# switcher.net
KiCad netlist of a schematic drawn in EAGLE
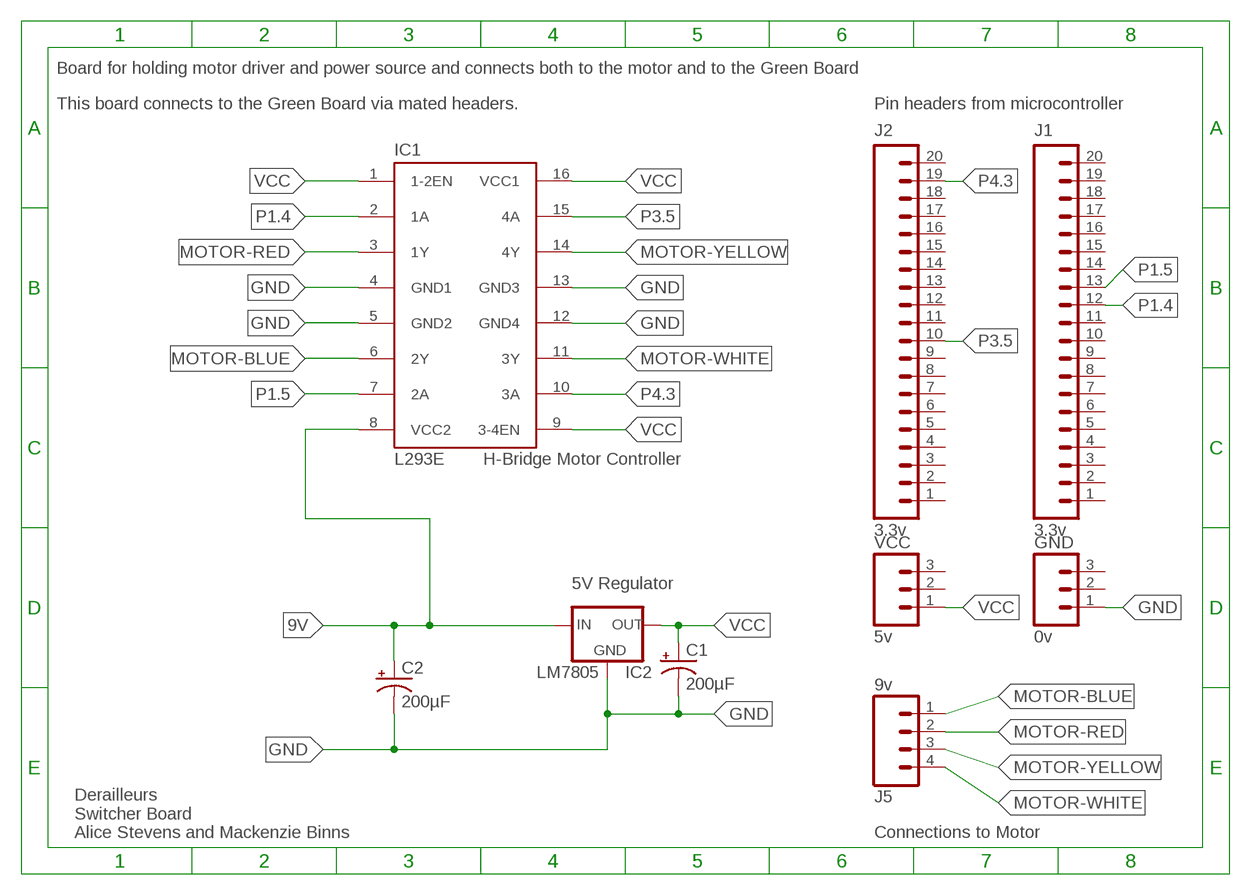
[diagram p0: schematic, sheet 1]

(export (version "E")
  (design (tool "Eeschema 10.0.6"))
  (components
    (comp (ref "C1")
      (value "200µF")
      (footprint "eagle-import:CPOL-RADIAL-100UF-25V")
      (libsource (lib "eagle-import") (part "CAP_POLPTH1"))
    )
    (comp (ref "C2")
      (value "200µF")
      (footprint "eagle-import:CPOL-RADIAL-100UF-25V")
      (libsource (lib "eagle-import") (part "CAP_POLPTH1"))
    )
    (comp (ref "GND")
      (value "0v")
      (footprint "eagle-import:1X03")
      (libsource (lib "eagle-import") (part "M03PTH"))
    )
    (comp (ref "IC1")
      (value "L293E")
      (footprint "eagle-import:DIL16")
      (fields (field (name "MF") "Arrow Electronics"))
      (libsource (lib "eagle-import") (part "L293E"))
    )
    (comp (ref "IC2")
      (value "78XXL")
      (footprint "eagle-import:78XXL")
      (libsource (lib "eagle-import") (part "78XXL"))
    )
    (comp (ref "J1")
      (value "3.3v")
      (footprint "eagle-import:1X20")
      (libsource (lib "eagle-import") (part "M20"))
    )
    (comp (ref "J2")
      (value "3.3v")
      (footprint "eagle-import:1X20")
      (libsource (lib "eagle-import") (part "M20"))
    )
    (comp (ref "J5")
      (value "9v")
      (footprint "eagle-import:1X04")
      (libsource (lib "eagle-import") (part "M04PTH"))
    )
    (comp (ref "VCC")
      (value "5v")
      (footprint "eagle-import:1X03")
      (libsource (lib "eagle-import") (part "M03PTH"))
    )
  )
  (nets
    (net (code "1") (name "9V") (class "Default")
      (node (ref "C2") (pin "1") (pinfunction "+_1") (pintype "passive"))
      (node (ref "IC1") (pin "8") (pinfunction "VCC2_8") (pintype "power_in"))
      (node (ref "IC2") (pin "IN") (pinfunction "IN_IN") (pintype "input"))
    )
    (net (code "2") (name "GND") (class "Default")
      (node (ref "C1") (pin "2") (pinfunction "-_2") (pintype "passive"))
      (node (ref "C2") (pin "2") (pinfunction "-_2") (pintype "passive"))
      (node (ref "GND") (pin "1") (pinfunction "1_1") (pintype "passive"))
      (node (ref "IC1") (pin "12") (pinfunction "GND4_12") (pintype "power_in"))
      (node (ref "IC1") (pin "13") (pinfunction "GND3_13") (pintype "power_in"))
      (node (ref "IC1") (pin "4") (pinfunction "GND1_4") (pintype "power_in"))
      (node (ref "IC1") (pin "5") (pinfunction "GND2_5") (pintype "power_in"))
      (node (ref "IC2") (pin "GND") (pinfunction "GND_GND") (pintype "input"))
    )
    (net (code "3") (name "MOTOR-BLUE") (class "Default")
      (node (ref "IC1") (pin "6") (pinfunction "2Y_6") (pintype "output"))
      (node (ref "J5") (pin "1") (pinfunction "1_1") (pintype "passive"))
    )
    (net (code "4") (name "MOTOR-RED") (class "Default")
      (node (ref "IC1") (pin "3") (pinfunction "1Y_3") (pintype "output"))
      (node (ref "J5") (pin "2") (pinfunction "2_2") (pintype "passive"))
    )
    (net (code "5") (name "MOTOR-WHITE") (class "Default")
      (node (ref "IC1") (pin "11") (pinfunction "3Y_11") (pintype "output"))
      (node (ref "J5") (pin "4") (pinfunction "4_4") (pintype "passive"))
    )
    (net (code "6") (name "MOTOR-YELLOW") (class "Default")
      (node (ref "IC1") (pin "14") (pinfunction "4Y_14") (pintype "output"))
      (node (ref "J5") (pin "3") (pinfunction "3_3") (pintype "passive"))
    )
    (net (code "7") (name "P1.4") (class "Default")
      (node (ref "IC1") (pin "2") (pinfunction "1A_2") (pintype "input"))
      (node (ref "J1") (pin "12") (pinfunction "12_12") (pintype "passive"))
    )
    (net (code "8") (name "P1.5") (class "Default")
      (node (ref "IC1") (pin "7") (pinfunction "2A_7") (pintype "input"))
      (node (ref "J1") (pin "13") (pinfunction "13_13") (pintype "passive"))
    )
    (net (code "9") (name "P3.5") (class "Default")
      (node (ref "IC1") (pin "15") (pinfunction "4A_15") (pintype "input"))
      (node (ref "J2") (pin "10") (pinfunction "10_10") (pintype "passive"))
    )
    (net (code "10") (name "P4.3") (class "Default")
      (node (ref "IC1") (pin "10") (pinfunction "3A_10") (pintype "input"))
      (node (ref "J2") (pin "19") (pinfunction "19_19") (pintype "passive"))
    )
    (net (code "11") (name "VCC") (class "Default")
      (node (ref "C1") (pin "1") (pinfunction "+_1") (pintype "passive"))
      (node (ref "IC1") (pin "1") (pinfunction "1-2EN_1") (pintype "input"))
      (node (ref "IC1") (pin "16") (pinfunction "VCC1_16") (pintype "power_in"))
      (node (ref "IC1") (pin "9") (pinfunction "3-4EN_9") (pintype "input"))
      (node (ref "IC2") (pin "OUT") (pinfunction "OUT_OUT") (pintype "passive"))
      (node (ref "VCC") (pin "1") (pinfunction "1_1") (pintype "passive"))
    )
    (net (code "12") (name "unconnected-(GND-Pad2)") (class "Default")
      (node (ref "GND") (pin "2") (pinfunction "2_2") (pintype "passive"))
    )
    (net (code "13") (name "unconnected-(GND-Pad3)") (class "Default")
      (node (ref "GND") (pin "3") (pinfunction "3_3") (pintype "passive"))
    )
    (net (code "14") (name "unconnected-(J1-Pad1)") (class "Default")
      (node (ref "J1") (pin "1") (pinfunction "1_1") (pintype "passive"))
    )
    (net (code "15") (name "unconnected-(J1-Pad2)") (class "Default")
      (node (ref "J1") (pin "2") (pinfunction "2_2") (pintype "passive"))
    )
    (net (code "16") (name "unconnected-(J1-Pad3)") (class "Default")
      (node (ref "J1") (pin "3") (pinfunction "3_3") (pintype "passive"))
    )
    (net (code "17") (name "unconnected-(J1-Pad4)") (class "Default")
      (node (ref "J1") (pin "4") (pinfunction "4_4") (pintype "passive"))
    )
    (net (code "18") (name "unconnected-(J1-Pad5)") (class "Default")
      (node (ref "J1") (pin "5") (pinfunction "5_5") (pintype "passive"))
    )
    (net (code "19") (name "unconnected-(J1-Pad6)") (class "Default")
      (node (ref "J1") (pin "6") (pinfunction "6_6") (pintype "passive"))
    )
    (net (code "20") (name "unconnected-(J1-Pad7)") (class "Default")
      (node (ref "J1") (pin "7") (pinfunction "7_7") (pintype "passive"))
    )
    (net (code "21") (name "unconnected-(J1-Pad8)") (class "Default")
      (node (ref "J1") (pin "8") (pinfunction "8_8") (pintype "passive"))
    )
    (net (code "22") (name "unconnected-(J1-Pad9)") (class "Default")
      (node (ref "J1") (pin "9") (pinfunction "9_9") (pintype "passive"))
    )
    (net (code "23") (name "unconnected-(J1-Pad10)") (class "Default")
      (node (ref "J1") (pin "10") (pinfunction "10_10") (pintype "passive"))
    )
    (net (code "24") (name "unconnected-(J1-Pad11)") (class "Default")
      (node (ref "J1") (pin "11") (pinfunction "11_11") (pintype "passive"))
    )
    (net (code "25") (name "unconnected-(J1-Pad14)") (class "Default")
      (node (ref "J1") (pin "14") (pinfunction "14_14") (pintype "passive"))
    )
    (net (code "26") (name "unconnected-(J1-Pad15)") (class "Default")
      (node (ref "J1") (pin "15") (pinfunction "15_15") (pintype "passive"))
    )
    (net (code "27") (name "unconnected-(J1-Pad16)") (class "Default")
      (node (ref "J1") (pin "16") (pinfunction "16_16") (pintype "passive"))
    )
    (net (code "28") (name "unconnected-(J1-Pad17)") (class "Default")
      (node (ref "J1") (pin "17") (pinfunction "17_17") (pintype "passive"))
    )
    (net (code "29") (name "unconnected-(J1-Pad18)") (class "Default")
      (node (ref "J1") (pin "18") (pinfunction "18_18") (pintype "passive"))
    )
    (net (code "30") (name "unconnected-(J1-Pad19)") (class "Default")
      (node (ref "J1") (pin "19") (pinfunction "19_19") (pintype "passive"))
    )
    (net (code "31") (name "unconnected-(J1-Pad20)") (class "Default")
      (node (ref "J1") (pin "20") (pinfunction "20_20") (pintype "passive"))
    )
    (net (code "32") (name "unconnected-(J2-Pad1)") (class "Default")
      (node (ref "J2") (pin "1") (pinfunction "1_1") (pintype "passive"))
    )
    (net (code "33") (name "unconnected-(J2-Pad2)") (class "Default")
      (node (ref "J2") (pin "2") (pinfunction "2_2") (pintype "passive"))
    )
    (net (code "34") (name "unconnected-(J2-Pad3)") (class "Default")
      (node (ref "J2") (pin "3") (pinfunction "3_3") (pintype "passive"))
    )
    (net (code "35") (name "unconnected-(J2-Pad4)") (class "Default")
      (node (ref "J2") (pin "4") (pinfunction "4_4") (pintype "passive"))
    )
    (net (code "36") (name "unconnected-(J2-Pad5)") (class "Default")
      (node (ref "J2") (pin "5") (pinfunction "5_5") (pintype "passive"))
    )
    (net (code "37") (name "unconnected-(J2-Pad6)") (class "Default")
      (node (ref "J2") (pin "6") (pinfunction "6_6") (pintype "passive"))
    )
    (net (code "38") (name "unconnected-(J2-Pad7)") (class "Default")
      (node (ref "J2") (pin "7") (pinfunction "7_7") (pintype "passive"))
    )
    (net (code "39") (name "unconnected-(J2-Pad8)") (class "Default")
      (node (ref "J2") (pin "8") (pinfunction "8_8") (pintype "passive"))
    )
    (net (code "40") (name "unconnected-(J2-Pad9)") (class "Default")
      (node (ref "J2") (pin "9") (pinfunction "9_9") (pintype "passive"))
    )
    (net (code "41") (name "unconnected-(J2-Pad11)") (class "Default")
      (node (ref "J2") (pin "11") (pinfunction "11_11") (pintype "passive"))
    )
    (net (code "42") (name "unconnected-(J2-Pad12)") (class "Default")
      (node (ref "J2") (pin "12") (pinfunction "12_12") (pintype "passive"))
    )
    (net (code "43") (name "unconnected-(J2-Pad13)") (class "Default")
      (node (ref "J2") (pin "13") (pinfunction "13_13") (pintype "passive"))
    )
    (net (code "44") (name "unconnected-(J2-Pad14)") (class "Default")
      (node (ref "J2") (pin "14") (pinfunction "14_14") (pintype "passive"))
    )
    (net (code "45") (name "unconnected-(J2-Pad15)") (class "Default")
      (node (ref "J2") (pin "15") (pinfunction "15_15") (pintype "passive"))
    )
    (net (code "46") (name "unconnected-(J2-Pad16)") (class "Default")
      (node (ref "J2") (pin "16") (pinfunction "16_16") (pintype "passive"))
    )
    (net (code "47") (name "unconnected-(J2-Pad17)") (class "Default")
      (node (ref "J2") (pin "17") (pinfunction "17_17") (pintype "passive"))
    )
    (net (code "48") (name "unconnected-(J2-Pad18)") (class "Default")
      (node (ref "J2") (pin "18") (pinfunction "18_18") (pintype "passive"))
    )
    (net (code "49") (name "unconnected-(J2-Pad20)") (class "Default")
      (node (ref "J2") (pin "20") (pinfunction "20_20") (pintype "passive"))
    )
    (net (code "50") (name "unconnected-(VCC-Pad2)") (class "Default")
      (node (ref "VCC") (pin "2") (pinfunction "2_2") (pintype "passive"))
    )
    (net (code "51") (name "unconnected-(VCC-Pad3)") (class "Default")
      (node (ref "VCC") (pin "3") (pinfunction "3_3") (pintype "passive"))
    )
  )
)
